# Rov3_zasilanie_v2.net
KiCad netlist of a schematic drawn in EAGLE
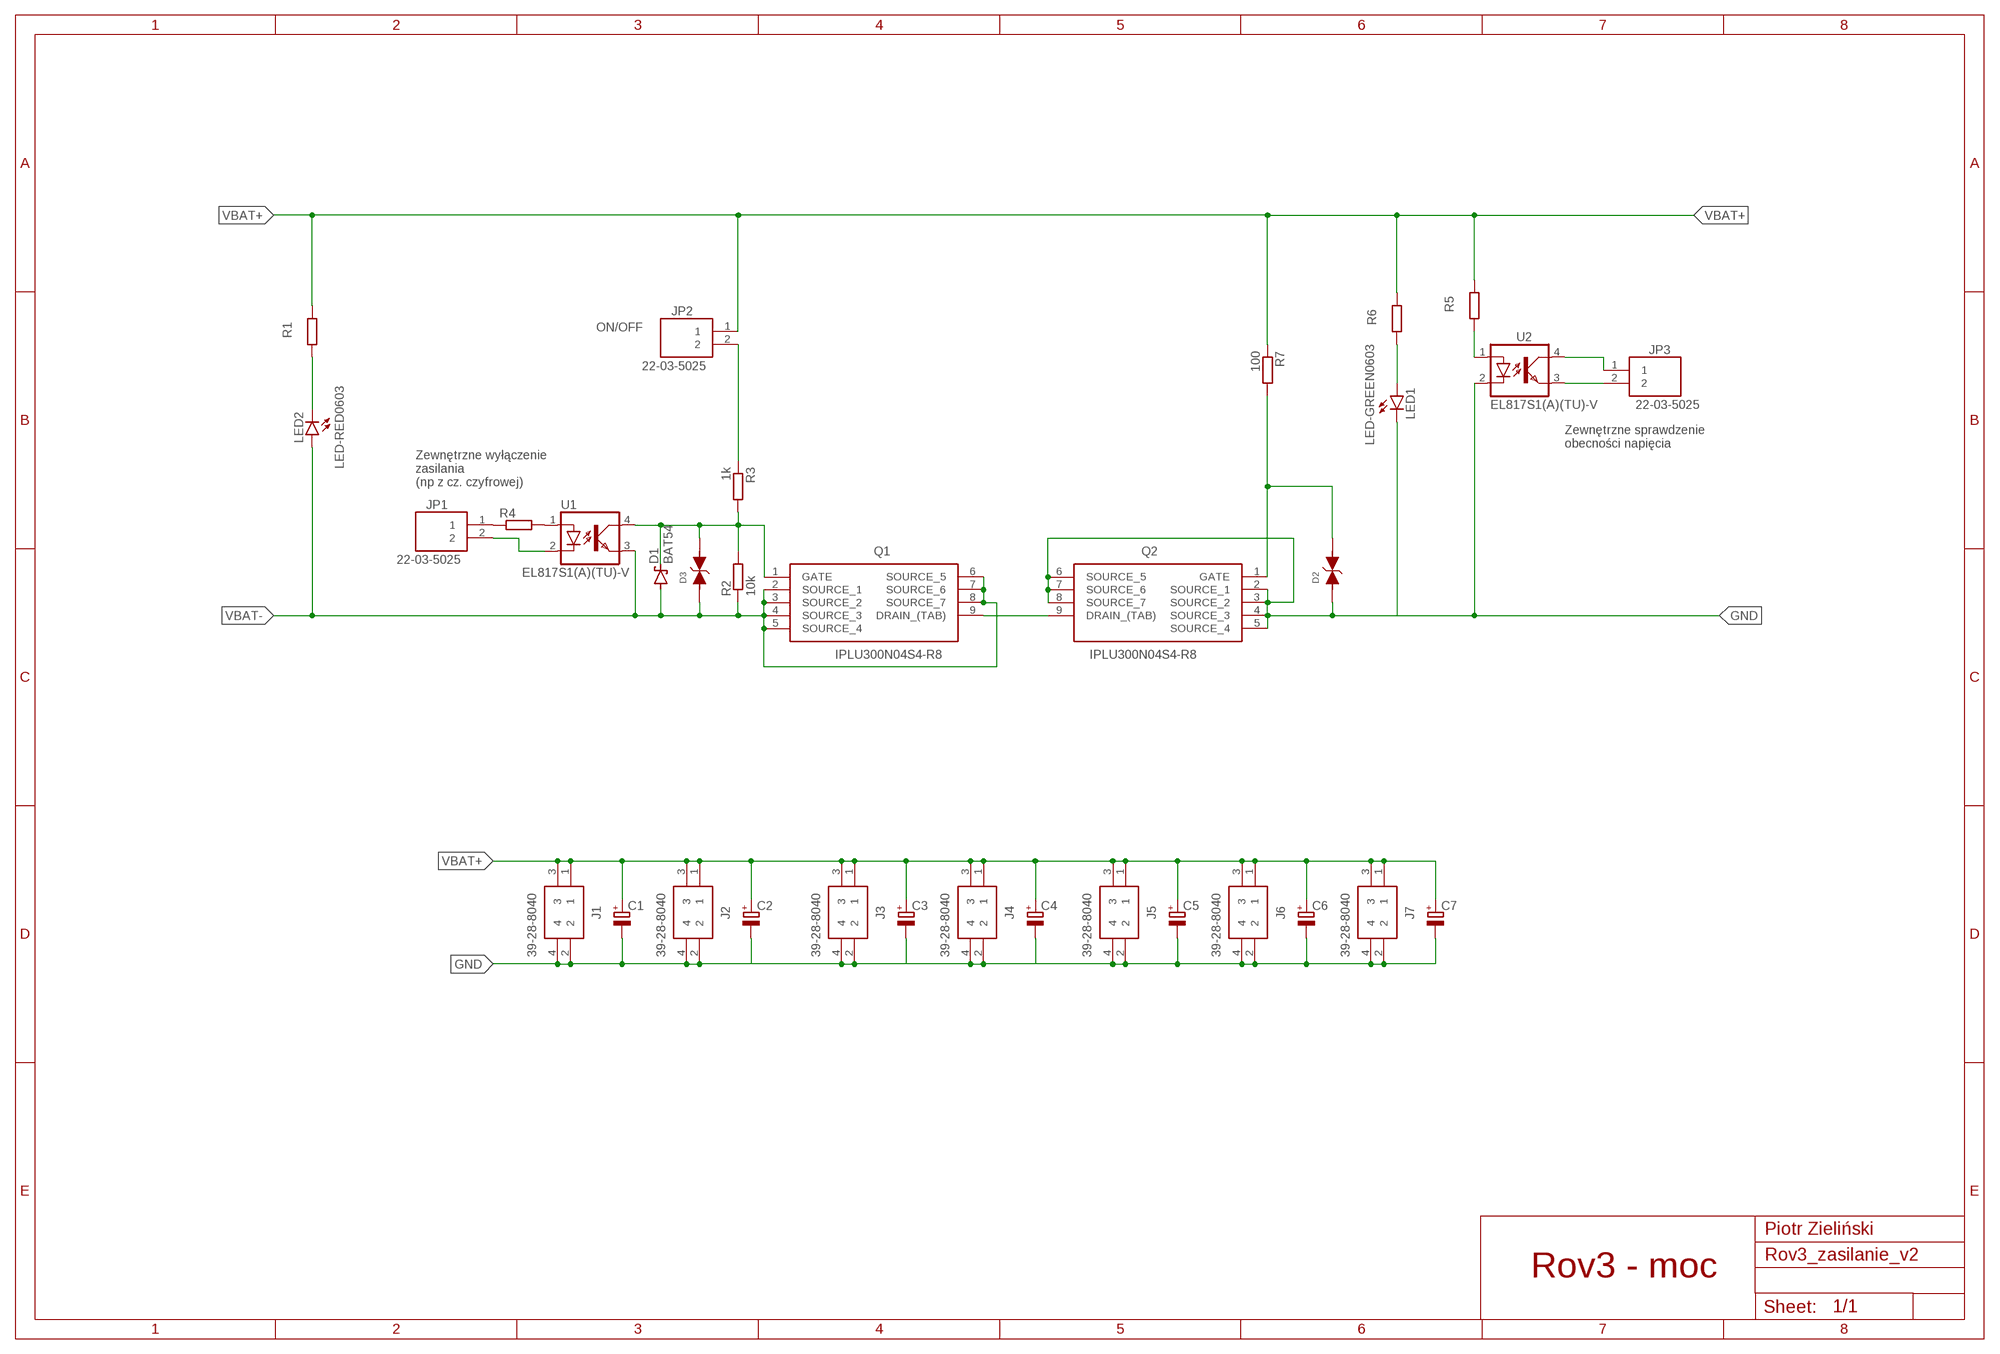
[diagram p0: schematic, sheet 1]

(export (version "E")
  (design (tool "Eeschema 10.0.6"))
  (components
    (comp (ref "C1")
      (value "CPOL-EUE5-10.5")
      (footprint "eagle-import:E5-10,5")
      (libsource (lib "eagle-import") (part "CPOL-EUE5-10.5"))
    )
    (comp (ref "C2")
      (value "CPOL-EUE5-10.5")
      (footprint "eagle-import:E5-10,5")
      (libsource (lib "eagle-import") (part "CPOL-EUE5-10.5"))
    )
    (comp (ref "C3")
      (value "CPOL-EUE5-10.5")
      (footprint "eagle-import:E5-10,5")
      (libsource (lib "eagle-import") (part "CPOL-EUE5-10.5"))
    )
    (comp (ref "C4")
      (value "CPOL-EUE5-10.5")
      (footprint "eagle-import:E5-10,5")
      (libsource (lib "eagle-import") (part "CPOL-EUE5-10.5"))
    )
    (comp (ref "C5")
      (value "CPOL-EUE5-10.5")
      (footprint "eagle-import:E5-10,5")
      (libsource (lib "eagle-import") (part "CPOL-EUE5-10.5"))
    )
    (comp (ref "C6")
      (value "CPOL-EUE5-10.5")
      (footprint "eagle-import:E5-10,5")
      (libsource (lib "eagle-import") (part "CPOL-EUE5-10.5"))
    )
    (comp (ref "C7")
      (value "CPOL-EUE5-10.5")
      (footprint "eagle-import:E5-10,5")
      (libsource (lib "eagle-import") (part "CPOL-EUE5-10.5"))
    )
    (comp (ref "D1")
      (value "BAT54")
      (footprint "eagle-import:SOT23")
      (libsource (lib "eagle-import") (part "BAT54"))
    )
    (comp (ref "D2")
      (value "WE-TVSP_BI_400W_824501221")
      (footprint "eagle-import:VARTVSP_SMA_DO-214AC")
      (libsource (lib "eagle-import") (part "WE-TVSP_BI_400W_824501221"))
    )
    (comp (ref "D3")
      (value "WE-TVSP_BI_400W_824501221")
      (footprint "eagle-import:VARTVSP_SMA_DO-214AC")
      (libsource (lib "eagle-import") (part "WE-TVSP_BI_400W_824501221"))
    )
    (comp (ref "J1")
      (value "39-28-8040")
      (footprint "eagle-import:MOLEX_2X2_PCB_SOCKET")
      (fields (field (name "MOUSER_PART_NUMBER") "538-39-28-8040"))
      (libsource (lib "eagle-import") (part "39-28-8040"))
    )
    (comp (ref "J2")
      (value "39-28-8040")
      (footprint "eagle-import:MOLEX_2X2_PCB_SOCKET")
      (fields (field (name "MOUSER_PART_NUMBER") "538-39-28-8040"))
      (libsource (lib "eagle-import") (part "39-28-8040"))
    )
    (comp (ref "J3")
      (value "39-28-8040")
      (footprint "eagle-import:MOLEX_2X2_PCB_SOCKET")
      (fields (field (name "MOUSER_PART_NUMBER") "538-39-28-8040"))
      (libsource (lib "eagle-import") (part "39-28-8040"))
    )
    (comp (ref "J4")
      (value "39-28-8040")
      (footprint "eagle-import:MOLEX_2X2_PCB_SOCKET")
      (fields (field (name "MOUSER_PART_NUMBER") "538-39-28-8040"))
      (libsource (lib "eagle-import") (part "39-28-8040"))
    )
    (comp (ref "J5")
      (value "39-28-8040")
      (footprint "eagle-import:MOLEX_2X2_PCB_SOCKET")
      (fields (field (name "MOUSER_PART_NUMBER") "538-39-28-8040"))
      (libsource (lib "eagle-import") (part "39-28-8040"))
    )
    (comp (ref "J6")
      (value "39-28-8040")
      (footprint "eagle-import:MOLEX_2X2_PCB_SOCKET")
      (fields (field (name "MOUSER_PART_NUMBER") "538-39-28-8040"))
      (libsource (lib "eagle-import") (part "39-28-8040"))
    )
    (comp (ref "J7")
      (value "39-28-8040")
      (footprint "eagle-import:MOLEX_2X2_PCB_SOCKET")
      (fields (field (name "MOUSER_PART_NUMBER") "538-39-28-8040"))
      (libsource (lib "eagle-import") (part "39-28-8040"))
    )
    (comp (ref "JP1")
      (value "22-03-5025")
      (footprint "eagle-import:2.50MM_MINI-SPOX_2PIN_PCB_SOCKET")
      (fields (field (name "MOUSER_PART_NUMBER") "538-22-03-5025"))
      (libsource (lib "eagle-import") (part "22-03-5025"))
    )
    (comp (ref "JP2")
      (value "22-03-5025")
      (footprint "eagle-import:2.50MM_MINI-SPOX_2PIN_PCB_SOCKET")
      (fields (field (name "MOUSER_PART_NUMBER") "538-22-03-5025"))
      (libsource (lib "eagle-import") (part "22-03-5025"))
    )
    (comp (ref "JP3")
      (value "22-03-5025")
      (footprint "eagle-import:2.50MM_MINI-SPOX_2PIN_PCB_SOCKET")
      (fields (field (name "MOUSER_PART_NUMBER") "538-22-03-5025"))
      (libsource (lib "eagle-import") (part "22-03-5025"))
    )
    (comp (ref "LED1")
      (value "LED-GREEN0603")
      (footprint "eagle-import:0603-GREEN")
      (libsource (lib "eagle-import") (part "LED-GREEN0603"))
    )
    (comp (ref "LED2")
      (value "LED-RED0603")
      (footprint "eagle-import:0603-RED")
      (libsource (lib "eagle-import") (part "LED-RED0603"))
    )
    (comp (ref "Q1")
      (value "IPLU300N04S4-R8")
      (footprint "eagle-import:PG-HSOF-8-1")
      (fields (field (name "MOUSER_PART_NUMBER") "726-IPLU300N04S4-R8"))
      (libsource (lib "eagle-import") (part "IPLU300N04S4-R8"))
    )
    (comp (ref "Q2")
      (value "IPLU300N04S4-R8")
      (footprint "eagle-import:PG-HSOF-8-1")
      (fields (field (name "MOUSER_PART_NUMBER") "726-IPLU300N04S4-R8"))
      (libsource (lib "eagle-import") (part "IPLU300N04S4-R8"))
    )
    (comp (ref "R1")
      (value "R-EU_R0805")
      (footprint "eagle-import:R0805")
      (libsource (lib "eagle-import") (part "R-EU_R0805"))
    )
    (comp (ref "R2")
      (value "10k")
      (footprint "eagle-import:R0805")
      (libsource (lib "eagle-import") (part "R-EU_R0805"))
    )
    (comp (ref "R3")
      (value "1k")
      (footprint "eagle-import:R0805")
      (libsource (lib "eagle-import") (part "R-EU_R0805"))
    )
    (comp (ref "R4")
      (value "R-EU_R0805")
      (footprint "eagle-import:R0805")
      (libsource (lib "eagle-import") (part "R-EU_R0805"))
    )
    (comp (ref "R5")
      (value "R-EU_R0805")
      (footprint "eagle-import:R0805")
      (libsource (lib "eagle-import") (part "R-EU_R0805"))
    )
    (comp (ref "R6")
      (value "R-EU_R0805")
      (footprint "eagle-import:R0805")
      (libsource (lib "eagle-import") (part "R-EU_R0805"))
    )
    (comp (ref "R7")
      (value "100")
      (footprint "eagle-import:R0805")
      (libsource (lib "eagle-import") (part "R-EU_R0805"))
    )
    (comp (ref "U1")
      (value "EL817S1(A)(TU)-V")
      (footprint "eagle-import:SOIC254P1030X390-4N_EL817S1(A)(TU)-V")
      (fields (field (name "MF") "Everlight Electronics") (field (name "MP") "EL817S1_A__TU_-V"))
      (libsource (lib "eagle-import") (part "EL817S1(A)(TU)-V"))
    )
    (comp (ref "U2")
      (value "EL817S1(A)(TU)-V")
      (footprint "eagle-import:SOIC254P1030X390-4N_EL817S1(A)(TU)-V")
      (fields (field (name "MF") "Everlight Electronics") (field (name "MP") "EL817S1_A__TU_-V"))
      (libsource (lib "eagle-import") (part "EL817S1(A)(TU)-V"))
    )
  )
  (nets
    (net (code "1") (name "GND") (class "Default")
      (node (ref "C1") (pin "-") (pinfunction "-_-") (pintype "passive"))
      (node (ref "C2") (pin "-") (pinfunction "-_-") (pintype "passive"))
      (node (ref "C3") (pin "-") (pinfunction "-_-") (pintype "passive"))
      (node (ref "C4") (pin "-") (pinfunction "-_-") (pintype "passive"))
      (node (ref "C5") (pin "-") (pinfunction "-_-") (pintype "passive"))
      (node (ref "C6") (pin "-") (pinfunction "-_-") (pintype "passive"))
      (node (ref "C7") (pin "-") (pinfunction "-_-") (pintype "passive"))
      (node (ref "D2") (pin "1") (pinfunction "1_1") (pintype "passive"))
      (node (ref "J1") (pin "2") (pinfunction "2_2") (pintype "bidirectional"))
      (node (ref "J1") (pin "4") (pinfunction "4_4") (pintype "bidirectional"))
      (node (ref "J2") (pin "2") (pinfunction "2_2") (pintype "bidirectional"))
      (node (ref "J2") (pin "4") (pinfunction "4_4") (pintype "bidirectional"))
      (node (ref "J3") (pin "2") (pinfunction "2_2") (pintype "bidirectional"))
      (node (ref "J3") (pin "4") (pinfunction "4_4") (pintype "bidirectional"))
      (node (ref "J4") (pin "2") (pinfunction "2_2") (pintype "bidirectional"))
      (node (ref "J4") (pin "4") (pinfunction "4_4") (pintype "bidirectional"))
      (node (ref "J5") (pin "2") (pinfunction "2_2") (pintype "bidirectional"))
      (node (ref "J5") (pin "4") (pinfunction "4_4") (pintype "bidirectional"))
      (node (ref "J6") (pin "2") (pinfunction "2_2") (pintype "bidirectional"))
      (node (ref "J6") (pin "4") (pinfunction "4_4") (pintype "bidirectional"))
      (node (ref "J7") (pin "2") (pinfunction "2_2") (pintype "bidirectional"))
      (node (ref "J7") (pin "4") (pinfunction "4_4") (pintype "bidirectional"))
      (node (ref "LED1") (pin "C") (pinfunction "C_C") (pintype "passive"))
      (node (ref "Q2") (pin "2") (pinfunction "SOURCE_1_2") (pintype "bidirectional"))
      (node (ref "Q2") (pin "3") (pinfunction "SOURCE_2_3") (pintype "bidirectional"))
      (node (ref "Q2") (pin "4") (pinfunction "SOURCE_3_4") (pintype "bidirectional"))
      (node (ref "Q2") (pin "5") (pinfunction "SOURCE_4_5") (pintype "bidirectional"))
      (node (ref "Q2") (pin "6") (pinfunction "SOURCE_5_6") (pintype "bidirectional"))
      (node (ref "Q2") (pin "7") (pinfunction "SOURCE_6_7") (pintype "bidirectional"))
      (node (ref "Q2") (pin "8") (pinfunction "SOURCE_7_8") (pintype "bidirectional"))
      (node (ref "U2") (pin "2") (pinfunction "C_2") (pintype "passive"))
    )
    (net (code "2") (name "Net-(D1-C)") (class "Default")
      (node (ref "D1") (pin "3") (pinfunction "C_3") (pintype "passive"))
      (node (ref "D3") (pin "2") (pinfunction "2_2") (pintype "passive"))
      (node (ref "Q1") (pin "1") (pinfunction "GATE_1") (pintype "bidirectional"))
      (node (ref "R2") (pin "2") (pinfunction "2_2") (pintype "passive"))
      (node (ref "R3") (pin "2") (pinfunction "2_2") (pintype "passive"))
      (node (ref "U1") (pin "4") (pinfunction "COL_4") (pintype "passive"))
    )
    (net (code "3") (name "Net-(JP1-Pad1)") (class "Default")
      (node (ref "JP1") (pin "1") (pinfunction "1_1") (pintype "bidirectional"))
      (node (ref "R4") (pin "1") (pinfunction "1_1") (pintype "passive"))
    )
    (net (code "4") (name "Net-(JP2-Pad2)") (class "Default")
      (node (ref "JP2") (pin "2") (pinfunction "2_2") (pintype "bidirectional"))
      (node (ref "R3") (pin "1") (pinfunction "1_1") (pintype "passive"))
    )
    (net (code "5") (name "Net-(LED1-PadA)") (class "Default")
      (node (ref "LED1") (pin "A") (pinfunction "A_A") (pintype "passive"))
      (node (ref "R6") (pin "1") (pinfunction "1_1") (pintype "passive"))
    )
    (net (code "6") (name "Net-(LED2-PadC)") (class "Default")
      (node (ref "LED2") (pin "C") (pinfunction "C_C") (pintype "passive"))
      (node (ref "R1") (pin "1") (pinfunction "1_1") (pintype "passive"))
    )
    (net (code "7") (name "Net-(Q1-DRAIN_(TAB))") (class "Default")
      (node (ref "Q1") (pin "9") (pinfunction "DRAIN_(TAB)_9") (pintype "bidirectional"))
      (node (ref "Q2") (pin "9") (pinfunction "DRAIN_(TAB)_9") (pintype "bidirectional"))
    )
    (net (code "8") (name "Net-(Q2-GATE)") (class "Default")
      (node (ref "D2") (pin "2") (pinfunction "2_2") (pintype "passive"))
      (node (ref "Q2") (pin "1") (pinfunction "GATE_1") (pintype "bidirectional"))
      (node (ref "R7") (pin "2") (pinfunction "2_2") (pintype "passive"))
    )
    (net (code "9") (name "Net-(U1-A)") (class "Default")
      (node (ref "R4") (pin "2") (pinfunction "2_2") (pintype "passive"))
      (node (ref "U1") (pin "1") (pinfunction "A_1") (pintype "passive"))
    )
    (net (code "10") (name "Net-(U1-C)") (class "Default")
      (node (ref "JP1") (pin "2") (pinfunction "2_2") (pintype "bidirectional"))
      (node (ref "U1") (pin "2") (pinfunction "C_2") (pintype "passive"))
    )
    (net (code "11") (name "Net-(U2-A)") (class "Default")
      (node (ref "R5") (pin "1") (pinfunction "1_1") (pintype "passive"))
      (node (ref "U2") (pin "1") (pinfunction "A_1") (pintype "passive"))
    )
    (net (code "12") (name "Net-(U2-COL)") (class "Default")
      (node (ref "JP3") (pin "1") (pinfunction "1_1") (pintype "bidirectional"))
      (node (ref "U2") (pin "4") (pinfunction "COL_4") (pintype "passive"))
    )
    (net (code "13") (name "Net-(U2-EMIT)") (class "Default")
      (node (ref "JP3") (pin "2") (pinfunction "2_2") (pintype "bidirectional"))
      (node (ref "U2") (pin "3") (pinfunction "EMIT_3") (pintype "passive"))
    )
    (net (code "14") (name "VBAT+") (class "Default")
      (node (ref "C1") (pin "+") (pinfunction "+_+") (pintype "passive"))
      (node (ref "C2") (pin "+") (pinfunction "+_+") (pintype "passive"))
      (node (ref "C3") (pin "+") (pinfunction "+_+") (pintype "passive"))
      (node (ref "C4") (pin "+") (pinfunction "+_+") (pintype "passive"))
      (node (ref "C5") (pin "+") (pinfunction "+_+") (pintype "passive"))
      (node (ref "C6") (pin "+") (pinfunction "+_+") (pintype "passive"))
      (node (ref "C7") (pin "+") (pinfunction "+_+") (pintype "passive"))
      (node (ref "J1") (pin "1") (pinfunction "1_1") (pintype "bidirectional"))
      (node (ref "J1") (pin "3") (pinfunction "3_3") (pintype "bidirectional"))
      (node (ref "J2") (pin "1") (pinfunction "1_1") (pintype "bidirectional"))
      (node (ref "J2") (pin "3") (pinfunction "3_3") (pintype "bidirectional"))
      (node (ref "J3") (pin "1") (pinfunction "1_1") (pintype "bidirectional"))
      (node (ref "J3") (pin "3") (pinfunction "3_3") (pintype "bidirectional"))
      (node (ref "J4") (pin "1") (pinfunction "1_1") (pintype "bidirectional"))
      (node (ref "J4") (pin "3") (pinfunction "3_3") (pintype "bidirectional"))
      (node (ref "J5") (pin "1") (pinfunction "1_1") (pintype "bidirectional"))
      (node (ref "J5") (pin "3") (pinfunction "3_3") (pintype "bidirectional"))
      (node (ref "J6") (pin "1") (pinfunction "1_1") (pintype "bidirectional"))
      (node (ref "J6") (pin "3") (pinfunction "3_3") (pintype "bidirectional"))
      (node (ref "J7") (pin "1") (pinfunction "1_1") (pintype "bidirectional"))
      (node (ref "J7") (pin "3") (pinfunction "3_3") (pintype "bidirectional"))
      (node (ref "JP2") (pin "1") (pinfunction "1_1") (pintype "bidirectional"))
      (node (ref "R1") (pin "2") (pinfunction "2_2") (pintype "passive"))
      (node (ref "R5") (pin "2") (pinfunction "2_2") (pintype "passive"))
      (node (ref "R6") (pin "2") (pinfunction "2_2") (pintype "passive"))
      (node (ref "R7") (pin "1") (pinfunction "1_1") (pintype "passive"))
    )
    (net (code "15") (name "VBAT-") (class "Default")
      (node (ref "D1") (pin "1") (pinfunction "A_1") (pintype "passive"))
      (node (ref "D3") (pin "1") (pinfunction "1_1") (pintype "passive"))
      (node (ref "LED2") (pin "A") (pinfunction "A_A") (pintype "passive"))
      (node (ref "Q1") (pin "2") (pinfunction "SOURCE_1_2") (pintype "bidirectional"))
      (node (ref "Q1") (pin "3") (pinfunction "SOURCE_2_3") (pintype "bidirectional"))
      (node (ref "Q1") (pin "4") (pinfunction "SOURCE_3_4") (pintype "bidirectional"))
      (node (ref "Q1") (pin "5") (pinfunction "SOURCE_4_5") (pintype "bidirectional"))
      (node (ref "Q1") (pin "6") (pinfunction "SOURCE_5_6") (pintype "bidirectional"))
      (node (ref "Q1") (pin "7") (pinfunction "SOURCE_6_7") (pintype "bidirectional"))
      (node (ref "Q1") (pin "8") (pinfunction "SOURCE_7_8") (pintype "bidirectional"))
      (node (ref "R2") (pin "1") (pinfunction "1_1") (pintype "passive"))
      (node (ref "U1") (pin "3") (pinfunction "EMIT_3") (pintype "passive"))
    )
  )
)
